# Sheet5.net
KiCad netlist of a schematic drawn in Altium Designer
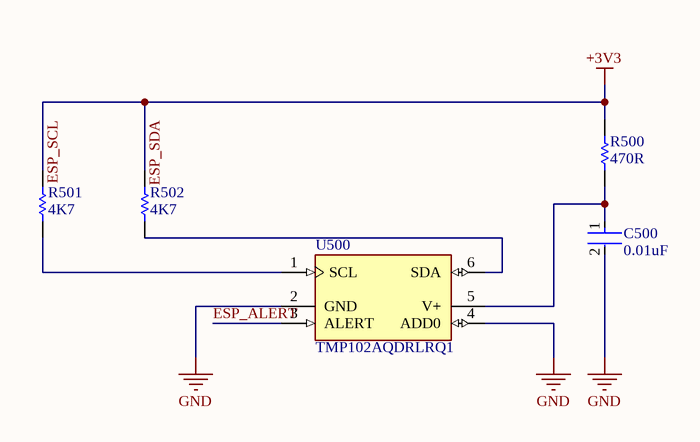
[diagram p0: Sheet5.SchDoc]

(export (version "E")
  (design (tool "Eeschema 10.0.6"))
  (components
    (comp (ref "C500")
      (value "0.01uF")
      (footprint "FP-GRM155-0_05-IPC_C")
      (description "Chip Multilayer Ceramic Capacitors for General Purpose, 0402, 10000pF, X7R, 15%, 10%, 50V")
      (fields (field (name "TOLERANCE") "10%") (field (name "VOLTAGE") "25V"))
      (libsource (lib "Altium Content Vault") (part "02cd4be3c70576c341d710602a673aa"))
    )
    (comp (ref "R500")
      (value "470R")
      (footprint "RESC1005X40X25ML05T10")
      (fields (field (name "PART NUMBER") "RC0402FR-07470RL") (field (name "MANUFACTURER") "Yageo / Phycomp"))
      (libsource (lib "Altium Content Vault") (part "RES"))
    )
    (comp (ref "R501")
      (value "4K7")
      (footprint "RESC1005X40X25NL05T10")
      (fields (field (name "MANUFACTURER") "Yageo / Phycomp") (field (name "PART NUMBER") "RC0402FR-074K7L"))
      (libsource (lib "Altium Content Vault") (part "RES"))
    )
    (comp (ref "R502")
      (value "4K7")
      (footprint "RESC1005X40X25NL05T10")
      (fields (field (name "MANUFACTURER") "Yageo / Phycomp") (field (name "PART NUMBER") "RC0402FR-074K7L"))
      (libsource (lib "Altium Content Vault") (part "RES"))
    )
    (comp (ref "U500")
      (value "TMP102AQDRLRQ1")
      (footprint "FP-DRL0006A-MFG")
      (description "SENSOR DIGITAL -40C-125C 6SOT")
      (libsource (lib "Altium Content Vault") (part "3a3e9e06997694bfdd4e09ba807ea6b"))
    )
  )
  (nets
    (net (code "1") (name "+3V3") (class "Default")
      (node (ref "R500") (pin "2") (pinfunction "2_2") (pintype "passive"))
      (node (ref "R501") (pin "2") (pinfunction "2_2") (pintype "passive"))
      (node (ref "R502") (pin "2") (pinfunction "2_2") (pintype "passive"))
    )
    (net (code "2") (name "/ESP_ALERT") (class "Default")
      (node (ref "U500") (pin "3") (pinfunction "ALERT_3") (pintype "input"))
    )
    (net (code "3") (name "GND") (class "Default")
      (node (ref "C500") (pin "2") (pinfunction "2_2") (pintype "passive"))
      (node (ref "U500") (pin "2") (pinfunction "GND_2") (pintype "power_in"))
      (node (ref "U500") (pin "4") (pinfunction "ADD0_4") (pintype "bidirectional"))
    )
    (net (code "4") (name "Net-(U500-SCL)") (class "Default")
      (node (ref "R501") (pin "1") (pinfunction "1_1") (pintype "passive"))
      (node (ref "U500") (pin "1") (pinfunction "SCL_1") (pintype "input"))
    )
    (net (code "5") (name "Net-(U500-SDA)") (class "Default")
      (node (ref "R502") (pin "1") (pinfunction "1_1") (pintype "passive"))
      (node (ref "U500") (pin "6") (pinfunction "SDA_6") (pintype "bidirectional"))
    )
    (net (code "6") (name "Net-(U500-V+)") (class "Default")
      (node (ref "C500") (pin "1") (pinfunction "1_1") (pintype "passive"))
      (node (ref "R500") (pin "1") (pinfunction "1_1") (pintype "passive"))
      (node (ref "U500") (pin "5") (pinfunction "V+_5") (pintype "passive"))
    )
  )
)
